# power.net
KiCad netlist of a schematic drawn in Altium Designer
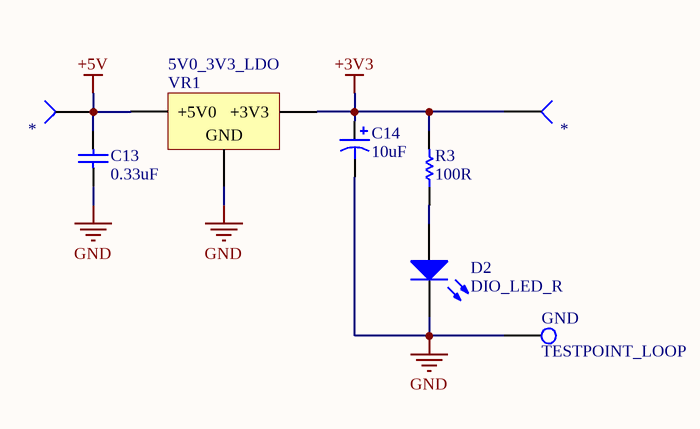
[diagram p0: power.SchDoc]

(export (version "E")
  (design (tool "Eeschema 10.0.6"))
  (components
    (comp (ref "3V3")
      (value "*")
      (footprint "TESTPOINT")
      (description "TESTPOINT_SMD")
      (libsource (lib "UWRT_Schematic_Library_2019") (part "*"))
    )
    (comp (ref "C13")
      (value "0.33uF")
      (footprint "CAPC0603(1608)55_N")
      (description "CAP CER 0.33UF 16V X7R 0603")
      (fields
        (field (name "MANUFACTURER") "Murata Electronics North America")
        (field (name "MPN") "GCM188R71C334KA37D")
      )
      (libsource (lib "UWRT_Schematic_Library_2019") (part "CAP_0.33uF_16V_0603"))
    )
    (comp (ref "C14")
      (value "10uF")
      (footprint "AVX-CAPC3528_V")
      (description "CAP TANT 10UF 20% 10V 1411")
      (fields (field (name "MPN") "F971A106MBAHT3") (field (name "MANUFACTURER") "AVX Corporation"))
      (libsource (lib "UWRT_Schematic_Library_2019") (part "CAP_10uF_1411_POL"))
    )
    (comp (ref "D2")
      (value "DIO_LED_R")
      (footprint "LED_0805_LINE")
      (description "LED RED DIFFUSED 0805 SMD")
      (fields (field (name "MANUFACTURER") "OSRAM") (field (name "MPN") "LS R976-NR-1"))
      (libsource (lib "UWRT_Schematic_Library_2019") (part "DIO_LED_R"))
    )
    (comp (ref "GND")
      (value "TESTPOINT_LOOP")
      (footprint "TESTPOINT_LOOP")
      (libsource (lib "UWRT_Schematic_Library_2019") (part "TESTPOINT_LOOP"))
    )
    (comp (ref "R3")
      (value "100R")
      (footprint "RESC0603(1608)_N")
      (description "RES SMD 100 OHM 1% 1/10W 0603")
      (fields (field (name "MANUFACTURER") "Yageo") (field (name "TOLERANCE") "1%"))
      (libsource (lib "UWRT_Schematic_Library_2019") (part "RES_100R_0603"))
    )
    (comp (ref "TESTPOINT_5V")
      (value "*")
      (footprint "TESTPOINT")
      (description "TESTPOINT_SMD")
      (libsource (lib "UWRT_Schematic_Library_2019") (part "*"))
    )
    (comp (ref "VR1")
      (value "5V0_3V3_LDO")
      (footprint "UWRT_Footprint_Library_2019:VOLTAGE_REGULATOR")
      (description "IC REG LINEAR 3.3V 1A DPAK")
      (fields (field (name "MANUFACTURER") "ON Semiconductor") (field (name "MPN") "NCP1117DT33T5G"))
      (libsource (lib "UWRT_Schematic_Library_2019") (part "5V0_3V3_LDO"))
    )
  )
  (nets
    (net (code "1") (name "+3V3") (class "Default")
      (node (ref "3V3") (pin "1") (pinfunction "=value_1") (pintype "passive"))
      (node (ref "C14") (pin "1") (pinfunction "1_1") (pintype "passive"))
      (node (ref "R3") (pin "2") (pinfunction "2_2") (pintype "passive"))
      (node (ref "VR1") (pin "2") (pinfunction "+3V3_2") (pintype "passive"))
    )
    (net (code "2") (name "+5V") (class "Default")
      (node (ref "C13") (pin "2") (pinfunction "2_2") (pintype "passive"))
      (node (ref "TESTPOINT_5V") (pin "1") (pinfunction "=value_1") (pintype "passive"))
      (node (ref "VR1") (pin "3") (pinfunction "+5V0_3") (pintype "passive"))
    )
    (net (code "3") (name "GND") (class "Default")
      (node (ref "C13") (pin "1") (pinfunction "1_1") (pintype "passive"))
      (node (ref "C14") (pin "2") (pinfunction "2_2") (pintype "passive"))
      (node (ref "D2") (pin "2") (pinfunction "K_2") (pintype "passive"))
      (node (ref "GND") (pin "1") (pinfunction "=value_1") (pintype "passive"))
      (node (ref "VR1") (pin "1") (pinfunction "GND_1") (pintype "passive"))
    )
    (net (code "4") (name "Net-(D2-A)") (class "Default")
      (node (ref "D2") (pin "1") (pinfunction "A_1") (pintype "passive"))
      (node (ref "R3") (pin "1") (pinfunction "1_1") (pintype "passive"))
    )
  )
)
